# SMD_Challenge_GT.net
KiCad netlist of a schematic drawn in EasyEDA Pro
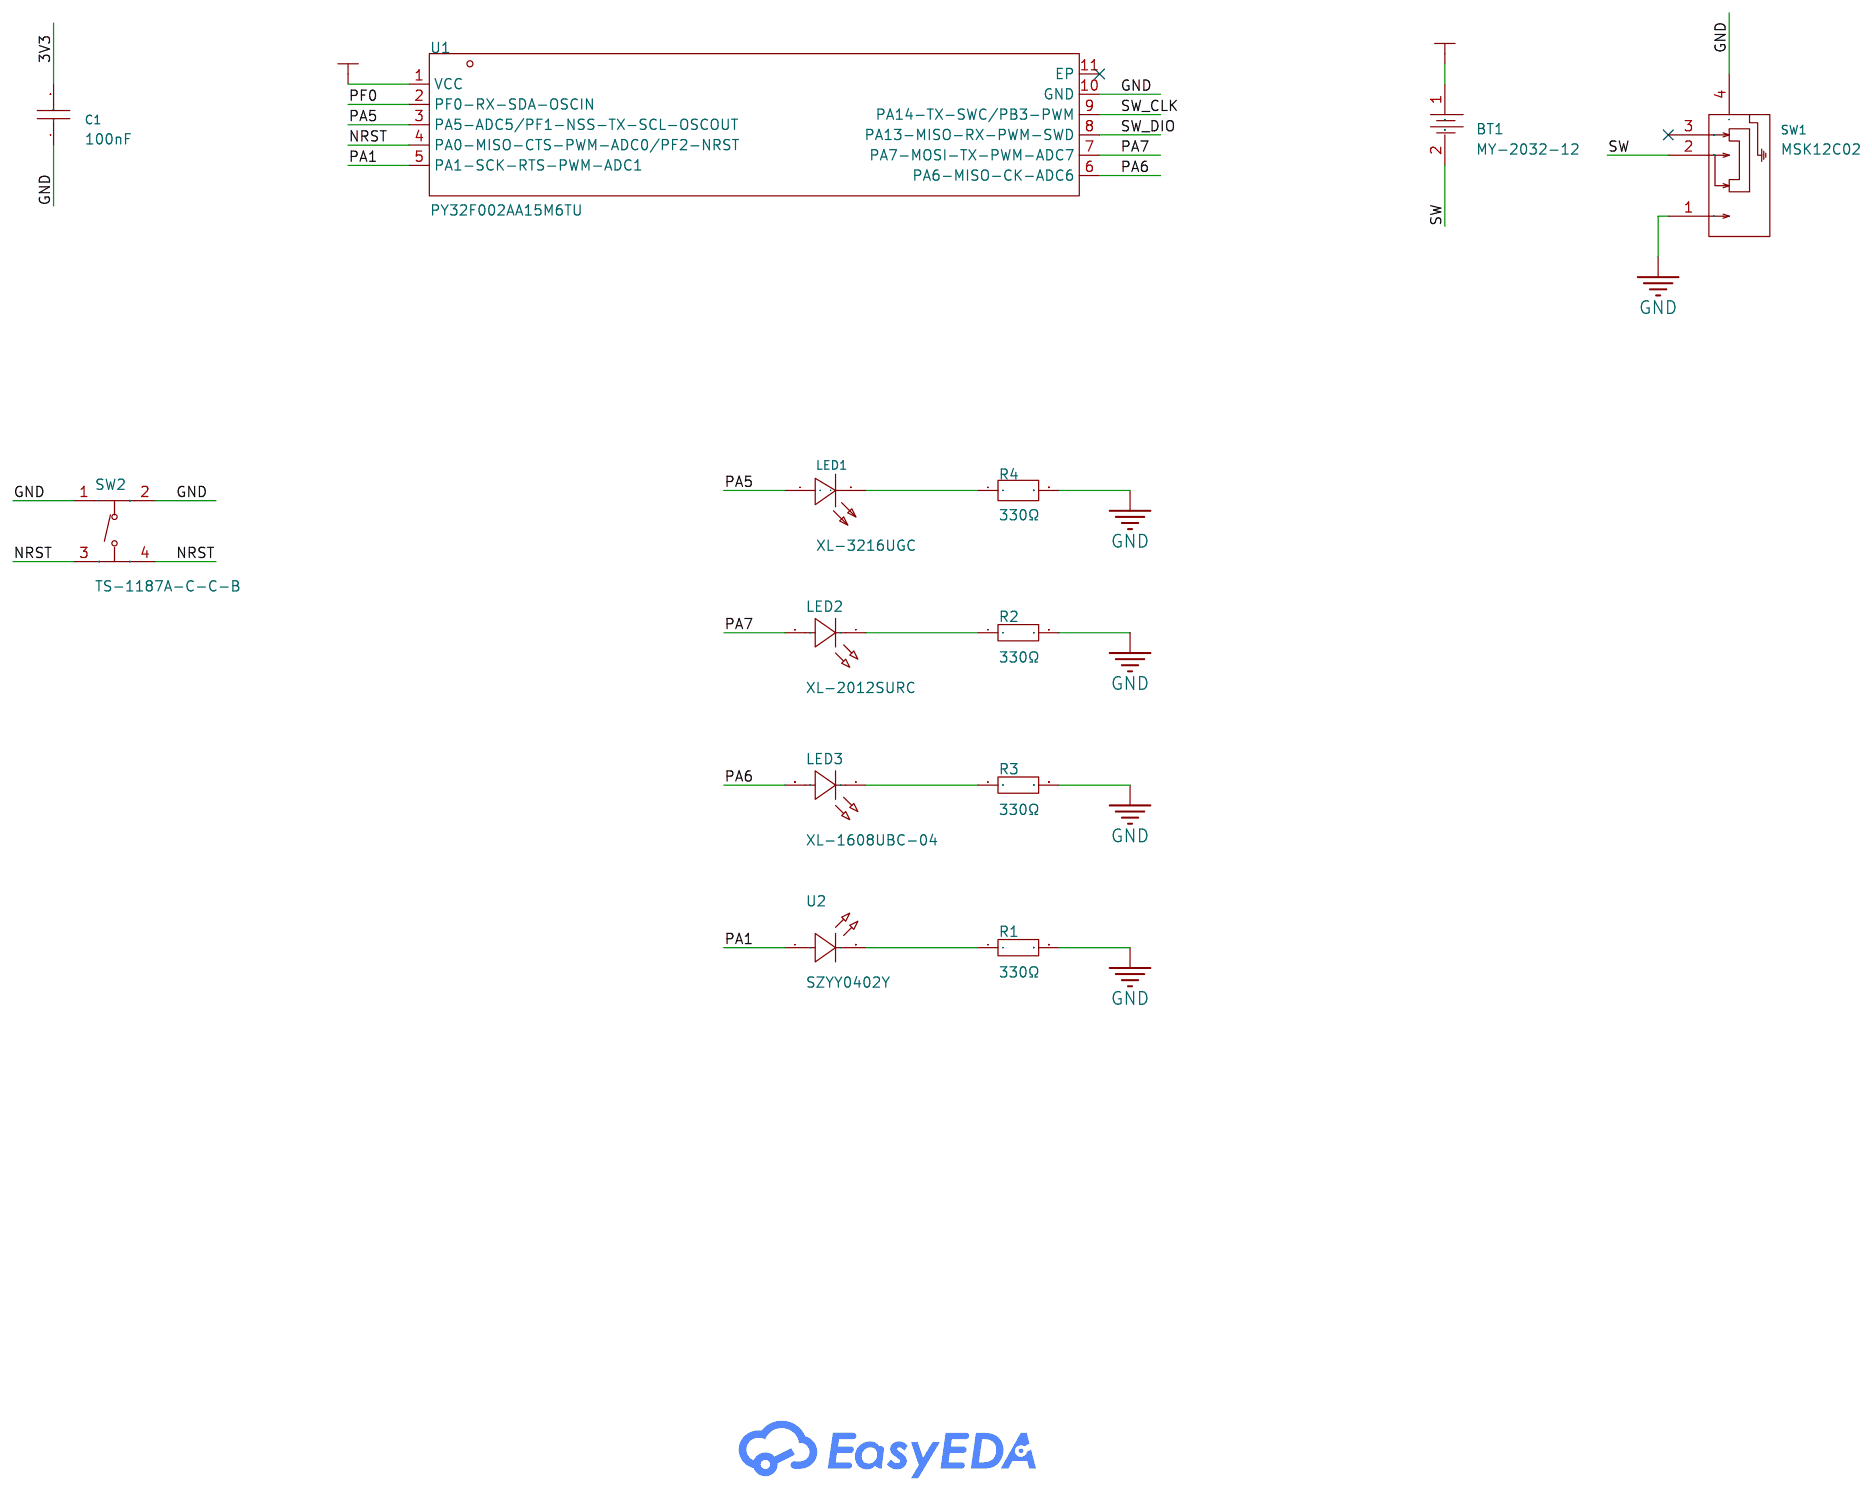
[diagram p0: schematic sheet]

(export (version "E")
  (design (tool "Eeschema 10.0.6"))
  (components
    (comp (ref "BT1")
      (value "MY-2032-12")
      (footprint "easyedapro:BAT-SMD_MY-2032-12")
      (fields (field (name "Manufacturer") "MYOUNG(美阳)"))
      (libsource (lib "easyedapro") (part "MY-2032-12"))
    )
    (comp (ref "C1")
      (value "100nF")
      (footprint "easyedapro:C0805")
      (description "Capacitance:100nF Tolerance:±10% Tolerance:±10% Voltage Rating:50V Temperature Coefficient:X7R")
      (fields (field (name "Manufacturer Part") "0805B104K500NT") (field (name "Manufacturer") "FH(风华)"))
      (libsource (lib "easyedapro") (part "0805B104K500NT"))
    )
    (comp (ref "LED1")
      (value "XL-3216UGC")
      (footprint "easyedapro:LED1206-R-RD_GREEN")
      (fields (field (name "Manufacturer") "XINGLIGHT(成兴光)"))
      (libsource (lib "easyedapro") (part "XL-3216UGC"))
    )
    (comp (ref "LED2")
      (value "XL-2012SURC")
      (footprint "easyedapro:LED0805-RD_RED")
      (fields (field (name "Manufacturer") "XINGLIGHT(成兴光)"))
      (libsource (lib "easyedapro") (part "XL-2012SURC"))
    )
    (comp (ref "LED3")
      (value "XL-1608UBC-04")
      (footprint "easyedapro:LED0603-RD_BLUE")
      (fields (field (name "Manufacturer") "XINGLIGHT(成兴光)"))
      (libsource (lib "easyedapro") (part "XL-1608UBC-04"))
    )
    (comp (ref "R1")
      (value "330Ω")
      (footprint "easyedapro:R0402")
      (fields (field (name "Manufacturer Part") "RC0402FR-07330RL") (field (name "Manufacturer") "YAGEO(国巨)"))
      (libsource (lib "easyedapro") (part "RC0402FR-07330RL"))
    )
    (comp (ref "R2")
      (value "330Ω")
      (footprint "easyedapro:R0805")
      (fields (field (name "Manufacturer Part") "RC0805FR-07330RL") (field (name "Manufacturer") "YAGEO(国巨)"))
      (libsource (lib "easyedapro") (part "RC0805FR-07330RL"))
    )
    (comp (ref "R3")
      (value "330Ω")
      (footprint "easyedapro:R0603")
      (fields (field (name "Manufacturer Part") "RC0603FR-07330RL") (field (name "Manufacturer") "YAGEO(国巨)"))
      (libsource (lib "easyedapro") (part "RC0603FR-07330RL"))
    )
    (comp (ref "R4")
      (value "330Ω")
      (footprint "easyedapro:R1206")
      (fields (field (name "Manufacturer Part") "FRC1206F3300TS") (field (name "Manufacturer") "FOJAN(富捷)"))
      (libsource (lib "easyedapro") (part "FRC1206F3300TS"))
    )
    (comp (ref "SW1")
      (value "MSK12C02")
      (footprint "easyedapro:SW-TH_MSK12C02")
      (fields (field (name "Manufacturer") "SHOU HAN(首韩)"))
      (libsource (lib "easyedapro") (part "MSK12C02"))
    )
    (comp (ref "SW2")
      (value "TS-1187A-C-C-B")
      (footprint "easyedapro:SW-SMD_4P-L5.1-W5.1-P3.70-LS6.5-TL_H1.7")
      (fields (field (name "Manufacturer") "XKB Connectivity(中国星坤)"))
      (libsource (lib "easyedapro") (part "TS-1187A-C-C-B"))
    )
    (comp (ref "U1")
      (value "PY32F002AA15M6TU")
      (footprint "easyedapro:ESSOP-10_L4.9-W3.9-P1.00-LS6.0-BL-EP")
      (fields (field (name "Manufacturer") "PUYA(普冉)"))
      (libsource (lib "easyedapro") (part "PY32F002AA15M6TU"))
    )
    (comp (ref "U2")
      (value "SZYY0402Y")
      (footprint "easyedapro:LED0402-FD_YELLOW")
      (fields (field (name "Manufacturer") "yongyu(永裕光电)"))
      (libsource (lib "easyedapro") (part "SZYY0402Y"))
    )
  )
  (nets
    (net (code "1") (name "/NRST") (class "Default")
      (node (ref "SW2") (pin "3") (pinfunction "C_3") (pintype "unspecified"))
      (node (ref "SW2") (pin "4") (pinfunction "D_4") (pintype "unspecified"))
      (node (ref "U1") (pin "4") (pinfunction "PA0-MISO-CTS-PWM-ADC0/PF2-NRST_4") (pintype "unspecified"))
    )
    (net (code "2") (name "/PA1") (class "Default")
      (node (ref "U1") (pin "5") (pinfunction "PA1-SCK-RTS-PWM-ADC1_5") (pintype "unspecified"))
      (node (ref "U2") (pin "1") (pinfunction "A_1") (pintype "input"))
    )
    (net (code "3") (name "/PA5") (class "Default")
      (node (ref "LED1") (pin "1") (pinfunction "A_1") (pintype "input"))
      (node (ref "U1") (pin "3") (pinfunction "PA5-ADC5/PF1-NSS-TX-SCL-OSCOUT_3") (pintype "unspecified"))
    )
    (net (code "4") (name "/PA6") (class "Default")
      (node (ref "LED3") (pin "2") (pinfunction "A_2") (pintype "unspecified"))
      (node (ref "U1") (pin "6") (pinfunction "PA6-MISO-CK-ADC6_6") (pintype "unspecified"))
    )
    (net (code "5") (name "/PA7") (class "Default")
      (node (ref "LED2") (pin "2") (pinfunction "A_2") (pintype "unspecified"))
      (node (ref "U1") (pin "7") (pinfunction "PA7-MOSI-TX-PWM-ADC7_7") (pintype "unspecified"))
    )
    (net (code "6") (name "/PF0") (class "Default")
      (node (ref "U1") (pin "2") (pinfunction "PF0-RX-SDA-OSCIN_2") (pintype "unspecified"))
    )
    (net (code "7") (name "/SW") (class "Default")
      (node (ref "BT1") (pin "2") (pinfunction "2_2") (pintype "input"))
      (node (ref "SW1") (pin "2") (pinfunction "2_2") (pintype "input"))
    )
    (net (code "8") (name "/SW_CLK") (class "Default")
      (node (ref "U1") (pin "9") (pinfunction "PA14-TX-SWC/PB3-PWM_9") (pintype "unspecified"))
    )
    (net (code "9") (name "/SW_DIO") (class "Default")
      (node (ref "U1") (pin "8") (pinfunction "PA13-MISO-RX-PWM-SWD_8") (pintype "unspecified"))
    )
    (net (code "10") (name "3V3") (class "Default")
      (node (ref "BT1") (pin "1") (pinfunction "1_1") (pintype "input"))
      (node (ref "C1") (pin "2") (pinfunction "2_2") (pintype "input"))
      (node (ref "U1") (pin "1") (pinfunction "VCC_1") (pintype "unspecified"))
    )
    (net (code "11") (name "GND") (class "Default")
      (node (ref "C1") (pin "1") (pinfunction "1_1") (pintype "input"))
      (node (ref "R1") (pin "2") (pinfunction "2_2") (pintype "input"))
      (node (ref "R2") (pin "2") (pinfunction "2_2") (pintype "input"))
      (node (ref "R3") (pin "2") (pinfunction "2_2") (pintype "input"))
      (node (ref "R4") (pin "2") (pinfunction "2_2") (pintype "unspecified"))
      (node (ref "SW1") (pin "1") (pinfunction "1_1") (pintype "input"))
      (node (ref "SW1") (pin "4") (pinfunction "4_4") (pintype "input"))
      (node (ref "SW2") (pin "1") (pinfunction "A_1") (pintype "unspecified"))
      (node (ref "SW2") (pin "2") (pinfunction "B_2") (pintype "unspecified"))
      (node (ref "U1") (pin "10") (pinfunction "GND_10") (pintype "unspecified"))
    )
    (net (code "12") (name "Net-(LED1-K)") (class "Default")
      (node (ref "LED1") (pin "2") (pinfunction "K_2") (pintype "input"))
      (node (ref "R4") (pin "1") (pinfunction "1_1") (pintype "unspecified"))
    )
    (net (code "13") (name "Net-(LED2-K)") (class "Default")
      (node (ref "LED2") (pin "1") (pinfunction "K_1") (pintype "unspecified"))
      (node (ref "R2") (pin "1") (pinfunction "1_1") (pintype "input"))
    )
    (net (code "14") (name "Net-(LED3-K)") (class "Default")
      (node (ref "LED3") (pin "1") (pinfunction "K_1") (pintype "unspecified"))
      (node (ref "R3") (pin "1") (pinfunction "1_1") (pintype "input"))
    )
    (net (code "15") (name "Net-(U2-K)") (class "Default")
      (node (ref "R1") (pin "1") (pinfunction "1_1") (pintype "input"))
      (node (ref "U2") (pin "2") (pinfunction "K_2") (pintype "input"))
    )
    (net (code "16") (name "unconnected-(SW1-Pad3)") (class "Default")
      (node (ref "SW1") (pin "3") (pinfunction "3_3") (pintype "input+no_connect"))
    )
    (net (code "17") (name "unconnected-(U1-EP-Pad11)") (class "Default")
      (node (ref "U1") (pin "11") (pinfunction "EP_11") (pintype "unspecified+no_connect"))
    )
  )
)
